# VauDUOv1_0.net
KiCad netlist of a schematic drawn in EAGLE
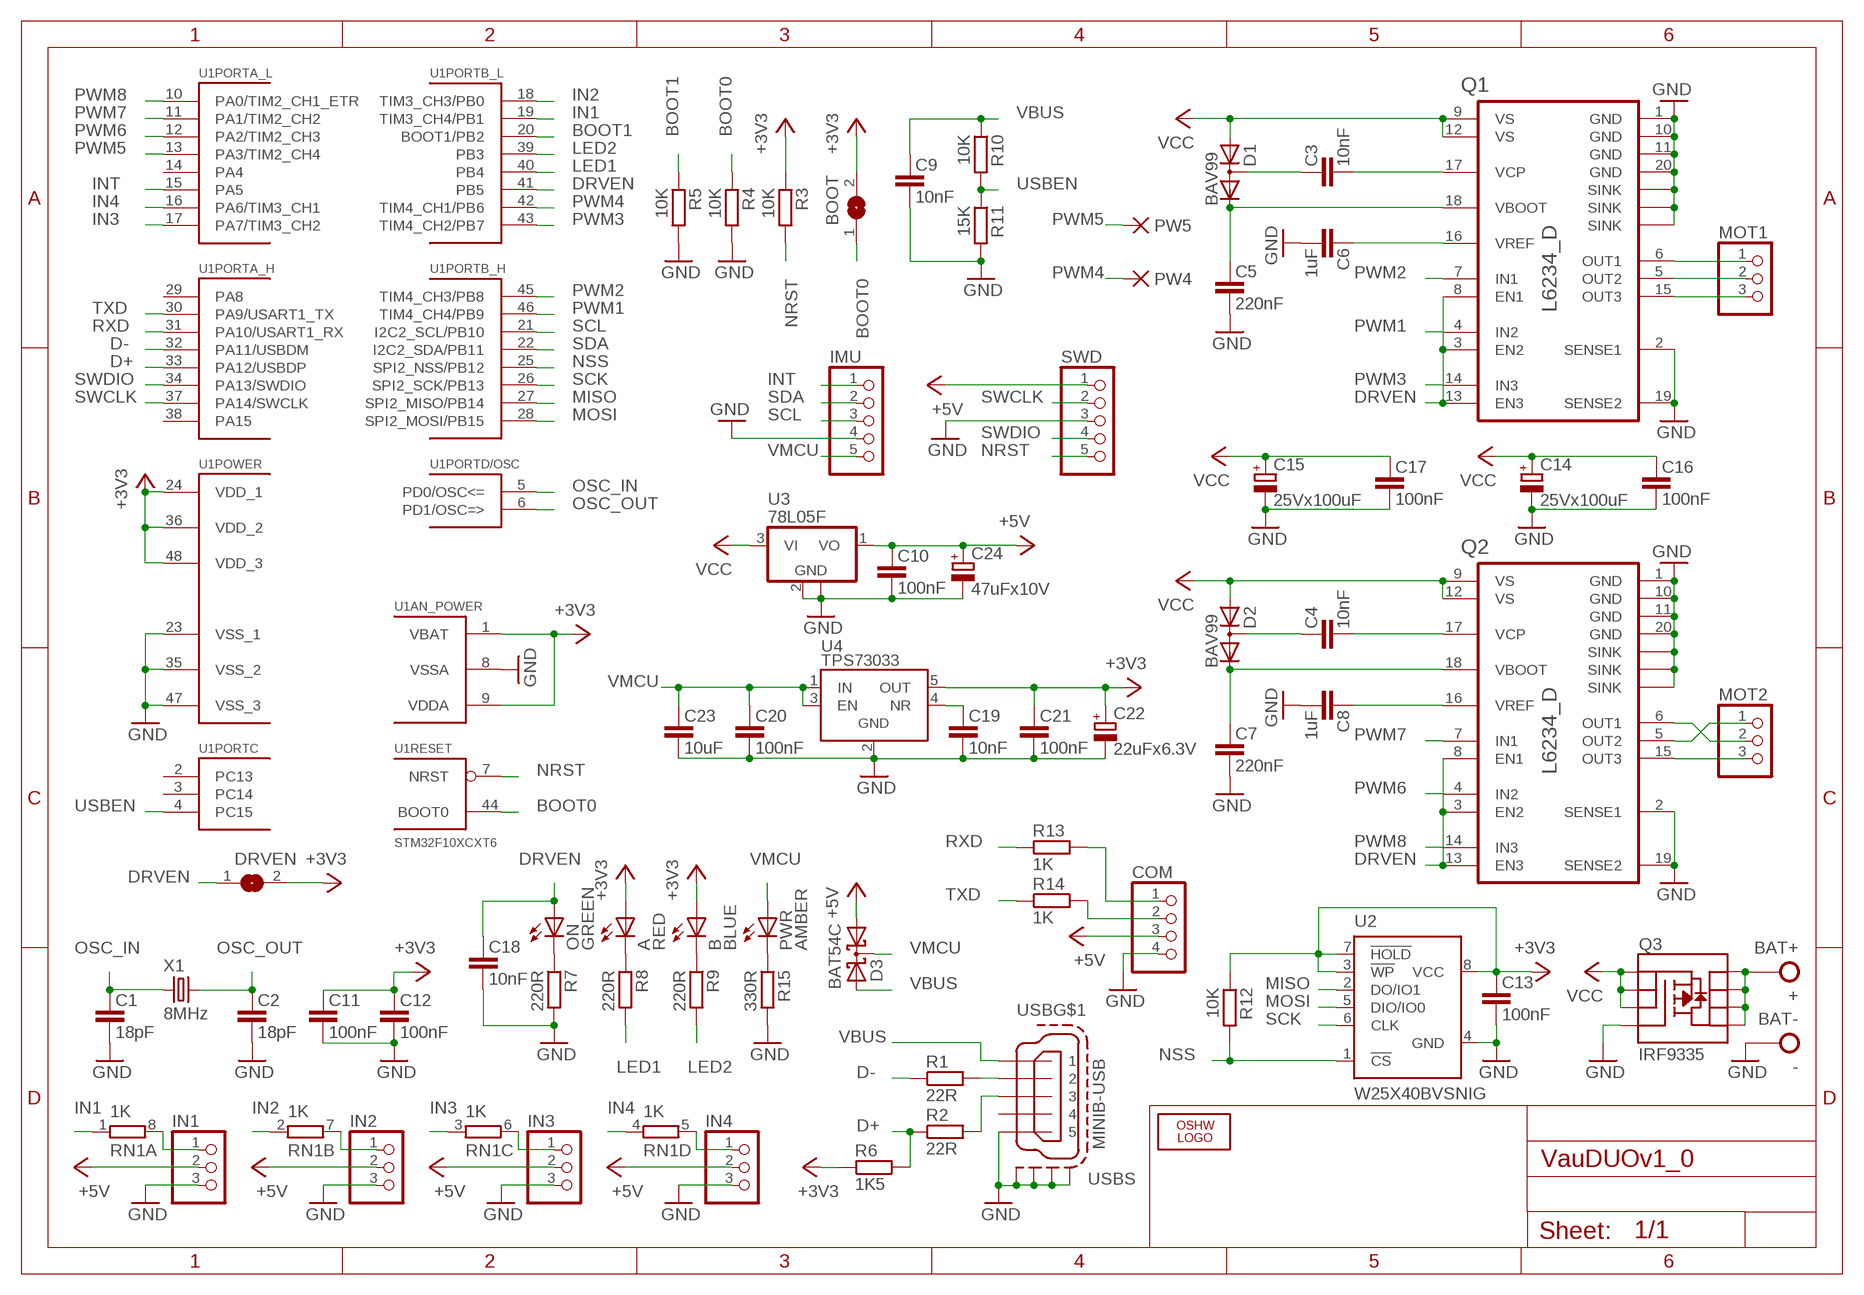
[diagram p0: schematic, sheet 1]

(export (version "E")
  (design (tool "Eeschema 10.0.6"))
  (components
    (comp (ref "+")
      (value "BAT+")
      (footprint "eagle-import:PAD20S")
      (libsource (lib "eagle-import") (part "POWER-PAD-20S"))
    )
    (comp (ref "-")
      (value "BAT-")
      (footprint "eagle-import:PAD20R")
      (libsource (lib "eagle-import") (part "POWER-PAD-20R"))
    )
    (comp (ref "A")
      (value "RED")
      (footprint "eagle-import:CHIPLED_0805")
      (libsource (lib "eagle-import") (part "LEDCHIPLED_0805"))
    )
    (comp (ref "B")
      (value "BLUE")
      (footprint "eagle-import:CHIPLED_0805")
      (libsource (lib "eagle-import") (part "LEDCHIPLED_0805"))
    )
    (comp (ref "BOOT")
      (value "SJ")
      (footprint "eagle-import:SJ")
      (libsource (lib "eagle-import") (part "SJ"))
    )
    (comp (ref "C1")
      (value "18pF")
      (footprint "eagle-import:C0603G")
      (libsource (lib "eagle-import") (part "C_EU_C0603G"))
    )
    (comp (ref "C2")
      (value "18pF")
      (footprint "eagle-import:C0603G")
      (libsource (lib "eagle-import") (part "C_EU_C0603G"))
    )
    (comp (ref "C3")
      (value "10nF")
      (footprint "eagle-import:C0603")
      (libsource (lib "eagle-import") (part "C_EU_C0603"))
    )
    (comp (ref "C4")
      (value "10nF")
      (footprint "eagle-import:C0603")
      (libsource (lib "eagle-import") (part "C_EU_C0603"))
    )
    (comp (ref "C5")
      (value "220nF")
      (footprint "eagle-import:C0603G")
      (libsource (lib "eagle-import") (part "C_EU_C0603G"))
    )
    (comp (ref "C6")
      (value "1uF")
      (footprint "eagle-import:C0603G")
      (libsource (lib "eagle-import") (part "C_EU_C0603G"))
    )
    (comp (ref "C7")
      (value "220nF")
      (footprint "eagle-import:C0603G")
      (libsource (lib "eagle-import") (part "C_EU_C0603G"))
    )
    (comp (ref "C8")
      (value "1uF")
      (footprint "eagle-import:C0603G")
      (libsource (lib "eagle-import") (part "C_EU_C0603G"))
    )
    (comp (ref "C9")
      (value "10nF")
      (footprint "eagle-import:C0603G")
      (libsource (lib "eagle-import") (part "C_EU_C0603G"))
    )
    (comp (ref "C10")
      (value "100nF")
      (footprint "eagle-import:C0603G")
      (libsource (lib "eagle-import") (part "C_EU_C0603G"))
    )
    (comp (ref "C11")
      (value "100nF")
      (footprint "eagle-import:C0603G")
      (libsource (lib "eagle-import") (part "C_EU_C0603G"))
    )
    (comp (ref "C12")
      (value "100nF")
      (footprint "eagle-import:C0603G")
      (libsource (lib "eagle-import") (part "C_EU_C0603G"))
    )
    (comp (ref "C13")
      (value "100nF")
      (footprint "eagle-import:C0603G")
      (libsource (lib "eagle-import") (part "C_EU_C0603G"))
    )
    (comp (ref "C14")
      (value "25Vx100uF")
      (footprint "eagle-import:E2,5-7")
      (libsource (lib "eagle-import") (part "CPOL-EUE2.5-7"))
    )
    (comp (ref "C15")
      (value "25Vx100uF")
      (footprint "eagle-import:E2,5-7")
      (libsource (lib "eagle-import") (part "CPOL-EUE2.5-7"))
    )
    (comp (ref "C16")
      (value "100nF")
      (footprint "eagle-import:C0603G")
      (libsource (lib "eagle-import") (part "C_EU_C0603G"))
    )
    (comp (ref "C17")
      (value "100nF")
      (footprint "eagle-import:C0603G")
      (libsource (lib "eagle-import") (part "C_EU_C0603G"))
    )
    (comp (ref "C18")
      (value "10nF")
      (footprint "eagle-import:C0603G")
      (libsource (lib "eagle-import") (part "C_EU_C0603G"))
    )
    (comp (ref "C19")
      (value "10nF")
      (footprint "eagle-import:C0603G")
      (libsource (lib "eagle-import") (part "C_EU_C0603G"))
    )
    (comp (ref "C20")
      (value "100nF")
      (footprint "eagle-import:C0603G")
      (libsource (lib "eagle-import") (part "C_EU_C0603G"))
    )
    (comp (ref "C21")
      (value "100nF")
      (footprint "eagle-import:C0603G")
      (libsource (lib "eagle-import") (part "C_EU_C0603G"))
    )
    (comp (ref "C22")
      (value "22uFx6.3V")
      (footprint "eagle-import:SMC_A")
      (libsource (lib "eagle-import") (part "CPOL-EUSMCA"))
    )
    (comp (ref "C23")
      (value "10uF")
      (footprint "eagle-import:C0805")
      (libsource (lib "eagle-import") (part "C_EU_C0805"))
    )
    (comp (ref "C24")
      (value "47uFx10V")
      (footprint "eagle-import:SMC_B")
      (libsource (lib "eagle-import") (part "CPOL-EUSMCB"))
    )
    (comp (ref "COM")
      (value "PINHD-1X4")
      (footprint "eagle-import:1X04")
      (libsource (lib "eagle-import") (part "PINHD-1X4"))
    )
    (comp (ref "D1")
      (value "BAV99")
      (footprint "eagle-import:SOT23")
      (libsource (lib "eagle-import") (part "BAV199"))
    )
    (comp (ref "D2")
      (value "BAV99")
      (footprint "eagle-import:SOT23")
      (libsource (lib "eagle-import") (part "BAV199"))
    )
    (comp (ref "D3")
      (value "BAT54C")
      (footprint "eagle-import:SOT23")
      (libsource (lib "eagle-import") (part "BAT54C"))
    )
    (comp (ref "DRVEN")
      (value "SJ")
      (footprint "eagle-import:SJ")
      (libsource (lib "eagle-import") (part "SJ"))
    )
    (comp (ref "IMU")
      (value "PINHD-1X5")
      (footprint "eagle-import:1X05")
      (libsource (lib "eagle-import") (part "PINHD-1X5"))
    )
    (comp (ref "IN1")
      (value "PINHD-1X3")
      (footprint "eagle-import:1X03")
      (libsource (lib "eagle-import") (part "PINHD-1X3"))
    )
    (comp (ref "IN2")
      (value "PINHD-1X3")
      (footprint "eagle-import:1X03")
      (libsource (lib "eagle-import") (part "PINHD-1X3"))
    )
    (comp (ref "IN3")
      (value "PINHD-1X3")
      (footprint "eagle-import:1X03")
      (libsource (lib "eagle-import") (part "PINHD-1X3"))
    )
    (comp (ref "IN4")
      (value "PINHD-1X3")
      (footprint "eagle-import:1X03")
      (libsource (lib "eagle-import") (part "PINHD-1X3"))
    )
    (comp (ref "LOGO1")
      (value "OSHW_LOGO_10MILX0350-NT")
      (footprint "eagle-import:OSHW_10X350_NOTEXT")
      (libsource (lib "eagle-import") (part "OSHW_LOGO_10MILX0350-NT"))
    )
    (comp (ref "MOT1")
      (value "PINHD-1X3MOT")
      (footprint "eagle-import:1X03M")
      (libsource (lib "eagle-import") (part "PINHD-1X3MOT"))
    )
    (comp (ref "MOT2")
      (value "PINHD-1X3MOT")
      (footprint "eagle-import:1X03M")
      (libsource (lib "eagle-import") (part "PINHD-1X3MOT"))
    )
    (comp (ref "ON")
      (value "GREEN")
      (footprint "eagle-import:CHIPLED_0805")
      (libsource (lib "eagle-import") (part "LEDCHIPLED_0805"))
    )
    (comp (ref "PW4")
      (value "PAD-SMD09R")
      (footprint "eagle-import:SMD09R")
      (libsource (lib "eagle-import") (part "PAD-SMD09R"))
    )
    (comp (ref "PW5")
      (value "PAD-SMD09R")
      (footprint "eagle-import:SMD09R")
      (libsource (lib "eagle-import") (part "PAD-SMD09R"))
    )
    (comp (ref "PWR")
      (value "AMBER")
      (footprint "eagle-import:CHIPLED_0805")
      (libsource (lib "eagle-import") (part "LEDCHIPLED_0805"))
    )
    (comp (ref "Q1")
      (value "L6234_D")
      (footprint "eagle-import:POWERSO20")
      (libsource (lib "eagle-import") (part "L6234_D"))
    )
    (comp (ref "Q2")
      (value "L6234_D")
      (footprint "eagle-import:POWERSO20")
      (libsource (lib "eagle-import") (part "L6234_D"))
    )
    (comp (ref "Q3")
      (value "IRF9335")
      (footprint "eagle-import:SOIC-8")
      (libsource (lib "eagle-import") (part "MOSFET-PCHANNEL-SOIC8"))
    )
    (comp (ref "R1")
      (value "22R")
      (footprint "eagle-import:R0603")
      (libsource (lib "eagle-import") (part "R_EU_R0603"))
    )
    (comp (ref "R2")
      (value "22R")
      (footprint "eagle-import:R0603")
      (libsource (lib "eagle-import") (part "R_EU_R0603"))
    )
    (comp (ref "R3")
      (value "10K")
      (footprint "eagle-import:R0603")
      (libsource (lib "eagle-import") (part "R_EU_R0603"))
    )
    (comp (ref "R4")
      (value "10K")
      (footprint "eagle-import:R0603G")
      (libsource (lib "eagle-import") (part "R_EU_R0603G"))
    )
    (comp (ref "R5")
      (value "10K")
      (footprint "eagle-import:R0603G")
      (libsource (lib "eagle-import") (part "R_EU_R0603G"))
    )
    (comp (ref "R6")
      (value "1K5")
      (footprint "eagle-import:R0603")
      (libsource (lib "eagle-import") (part "R_EU_R0603"))
    )
    (comp (ref "R7")
      (value "220R")
      (footprint "eagle-import:R0603G")
      (libsource (lib "eagle-import") (part "R_EU_R0603G"))
    )
    (comp (ref "R8")
      (value "220R")
      (footprint "eagle-import:R0603")
      (libsource (lib "eagle-import") (part "R_EU_R0603"))
    )
    (comp (ref "R9")
      (value "220R")
      (footprint "eagle-import:R0603")
      (libsource (lib "eagle-import") (part "R_EU_R0603"))
    )
    (comp (ref "R10")
      (value "10K")
      (footprint "eagle-import:R0603")
      (libsource (lib "eagle-import") (part "R_EU_R0603"))
    )
    (comp (ref "R11")
      (value "15K")
      (footprint "eagle-import:R0603G")
      (libsource (lib "eagle-import") (part "R_EU_R0603G"))
    )
    (comp (ref "R12")
      (value "10K")
      (footprint "eagle-import:R0603")
      (libsource (lib "eagle-import") (part "R_EU_R0603"))
    )
    (comp (ref "R13")
      (value "1K")
      (footprint "eagle-import:R0603")
      (libsource (lib "eagle-import") (part "R_EU_R0603"))
    )
    (comp (ref "R14")
      (value "1K")
      (footprint "eagle-import:R0603")
      (libsource (lib "eagle-import") (part "R_EU_R0603"))
    )
    (comp (ref "R15")
      (value "330R")
      (footprint "eagle-import:R0603")
      (libsource (lib "eagle-import") (part "R_EU_R0603"))
    )
    (comp (ref "RN1")
      (value "1K")
      (footprint "eagle-import:CAY16")
      (libsource (lib "eagle-import") (part "4R-NCAY16"))
    )
    (comp (ref "SWD")
      (value "PINHD-1X5")
      (footprint "eagle-import:1X05")
      (libsource (lib "eagle-import") (part "PINHD-1X5"))
    )
    (comp (ref "U1")
      (value "STM32F10XCXT6")
      (footprint "eagle-import:LQFP48")
      (libsource (lib "eagle-import") (part "STM32F10XCXT6"))
    )
    (comp (ref "U2")
      (value "W25X40BVSNIG")
      (footprint "eagle-import:SOIC-8")
      (libsource (lib "eagle-import") (part "W25X40BVSNIG"))
    )
    (comp (ref "U3")
      (value "78L05F")
      (footprint "eagle-import:SOT89")
      (libsource (lib "eagle-import") (part "78LF05"))
    )
    (comp (ref "U4")
      (value "TPS73033")
      (footprint "eagle-import:SOT23-5")
      (libsource (lib "eagle-import") (part "TPS769XX"))
    )
    (comp (ref "USB")
      (value "MINIB-USB")
      (footprint "eagle-import:32005-201")
      (libsource (lib "eagle-import") (part "MINI-USB-SCHIELD-32005-201"))
    )
    (comp (ref "X1")
      (value "8MHz")
      (footprint "eagle-import:HC49_S")
      (libsource (lib "eagle-import") (part "CRYSTALHC49S"))
    )
  )
  (nets
    (net (code "1") (name "+3V3") (class "Default")
      (node (ref "A") (pin "A") (pinfunction "A_A") (pintype "passive"))
      (node (ref "B") (pin "A") (pinfunction "A_A") (pintype "passive"))
      (node (ref "BOOT") (pin "2") (pinfunction "2_2") (pintype "passive"))
      (node (ref "C11") (pin "1") (pinfunction "1_1") (pintype "passive"))
      (node (ref "C12") (pin "1") (pinfunction "1_1") (pintype "passive"))
      (node (ref "C13") (pin "1") (pinfunction "1_1") (pintype "passive"))
      (node (ref "C21") (pin "1") (pinfunction "1_1") (pintype "passive"))
      (node (ref "C22") (pin "+") (pinfunction "+_+") (pintype "passive"))
      (node (ref "DRVEN") (pin "2") (pinfunction "2_2") (pintype "passive"))
      (node (ref "R12") (pin "1") (pinfunction "1_1") (pintype "passive"))
      (node (ref "R3") (pin "1") (pinfunction "1_1") (pintype "passive"))
      (node (ref "R6") (pin "1") (pinfunction "1_1") (pintype "passive"))
      (node (ref "U1") (pin "1") (pinfunction "VBAT_1") (pintype "power_in"))
      (node (ref "U1") (pin "24") (pinfunction "VDD_1_24") (pintype "power_in"))
      (node (ref "U1") (pin "36") (pinfunction "VDD_2_36") (pintype "power_in"))
      (node (ref "U1") (pin "48") (pinfunction "VDD_3_48") (pintype "power_in"))
      (node (ref "U1") (pin "9") (pinfunction "VDDA_9") (pintype "power_in"))
      (node (ref "U2") (pin "3") (pinfunction "~{WP}_3") (pintype "input"))
      (node (ref "U2") (pin "7") (pinfunction "~{HOLD}_7") (pintype "input"))
      (node (ref "U2") (pin "8") (pinfunction "VCC_8") (pintype "power_in"))
      (node (ref "U4") (pin "5") (pinfunction "OUT_5") (pintype "power_in"))
    )
    (net (code "2") (name "+5V") (class "Default")
      (node (ref "C10") (pin "1") (pinfunction "1_1") (pintype "passive"))
      (node (ref "C24") (pin "+") (pinfunction "+_+") (pintype "passive"))
      (node (ref "COM") (pin "3") (pinfunction "3_3") (pintype "passive"))
      (node (ref "D3") (pin "1") (pinfunction "A1_1") (pintype "passive"))
      (node (ref "IN1") (pin "2") (pinfunction "2_2") (pintype "passive"))
      (node (ref "IN2") (pin "2") (pinfunction "2_2") (pintype "passive"))
      (node (ref "IN3") (pin "2") (pinfunction "2_2") (pintype "passive"))
      (node (ref "IN4") (pin "2") (pinfunction "2_2") (pintype "passive"))
      (node (ref "SWD") (pin "1") (pinfunction "1_1") (pintype "passive"))
      (node (ref "U3") (pin "1") (pinfunction "VO_1") (pintype "passive"))
    )
    (net (code "3") (name "/BOOT0") (class "Default")
      (node (ref "BOOT") (pin "1") (pinfunction "1_1") (pintype "passive"))
      (node (ref "R4") (pin "1") (pinfunction "1_1") (pintype "passive"))
      (node (ref "U1") (pin "44") (pinfunction "BOOT0_44") (pintype "input"))
    )
    (net (code "4") (name "/BOOT1") (class "Default")
      (node (ref "R5") (pin "1") (pinfunction "1_1") (pintype "passive"))
      (node (ref "U1") (pin "20") (pinfunction "BOOT1/PB2_20") (pintype "bidirectional"))
    )
    (net (code "5") (name "/D+") (class "Default")
      (node (ref "R2") (pin "1") (pinfunction "1_1") (pintype "passive"))
      (node (ref "R6") (pin "2") (pinfunction "2_2") (pintype "passive"))
      (node (ref "U1") (pin "33") (pinfunction "PA12/USBDP_33") (pintype "bidirectional"))
    )
    (net (code "6") (name "/D-") (class "Default")
      (node (ref "R1") (pin "1") (pinfunction "1_1") (pintype "passive"))
      (node (ref "U1") (pin "32") (pinfunction "PA11/USBDM_32") (pintype "bidirectional"))
    )
    (net (code "7") (name "/DRVEN") (class "Default")
      (node (ref "C18") (pin "1") (pinfunction "1_1") (pintype "passive"))
      (node (ref "DRVEN") (pin "1") (pinfunction "1_1") (pintype "passive"))
      (node (ref "ON") (pin "A") (pinfunction "A_A") (pintype "passive"))
      (node (ref "Q1") (pin "13") (pinfunction "EN3_13") (pintype "input"))
      (node (ref "Q1") (pin "3") (pinfunction "EN2_3") (pintype "input"))
      (node (ref "Q1") (pin "8") (pinfunction "EN1_8") (pintype "input"))
      (node (ref "Q2") (pin "13") (pinfunction "EN3_13") (pintype "input"))
      (node (ref "Q2") (pin "3") (pinfunction "EN2_3") (pintype "input"))
      (node (ref "Q2") (pin "8") (pinfunction "EN1_8") (pintype "input"))
      (node (ref "U1") (pin "41") (pinfunction "PB5_41") (pintype "bidirectional"))
    )
    (net (code "8") (name "/IN1") (class "Default")
      (node (ref "RN1") (pin "1") (pinfunction "1_1") (pintype "passive"))
      (node (ref "U1") (pin "19") (pinfunction "TIM3_CH4/PB1_19") (pintype "bidirectional"))
    )
    (net (code "9") (name "/IN2") (class "Default")
      (node (ref "RN1") (pin "2") (pinfunction "1_2") (pintype "passive"))
      (node (ref "U1") (pin "18") (pinfunction "TIM3_CH3/PB0_18") (pintype "bidirectional"))
    )
    (net (code "10") (name "/IN3") (class "Default")
      (node (ref "RN1") (pin "3") (pinfunction "1_3") (pintype "passive"))
      (node (ref "U1") (pin "17") (pinfunction "PA7/TIM3_CH2_17") (pintype "bidirectional"))
    )
    (net (code "11") (name "/IN4") (class "Default")
      (node (ref "RN1") (pin "4") (pinfunction "1_4") (pintype "passive"))
      (node (ref "U1") (pin "16") (pinfunction "PA6/TIM3_CH1_16") (pintype "bidirectional"))
    )
    (net (code "12") (name "/INT") (class "Default")
      (node (ref "IMU") (pin "1") (pinfunction "1_1") (pintype "passive"))
      (node (ref "U1") (pin "15") (pinfunction "PA5_15") (pintype "bidirectional"))
    )
    (net (code "13") (name "/LED1") (class "Default")
      (node (ref "R8") (pin "2") (pinfunction "2_2") (pintype "passive"))
      (node (ref "U1") (pin "40") (pinfunction "PB4_40") (pintype "bidirectional"))
    )
    (net (code "14") (name "/LED2") (class "Default")
      (node (ref "R9") (pin "2") (pinfunction "2_2") (pintype "passive"))
      (node (ref "U1") (pin "39") (pinfunction "PB3_39") (pintype "bidirectional"))
    )
    (net (code "15") (name "/MISO") (class "Default")
      (node (ref "U1") (pin "27") (pinfunction "SPI2_MISO/PB14_27") (pintype "bidirectional"))
      (node (ref "U2") (pin "2") (pinfunction "DO/IO1_2") (pintype "output"))
    )
    (net (code "16") (name "/MOSI") (class "Default")
      (node (ref "U1") (pin "28") (pinfunction "SPI2_MOSI/PB15_28") (pintype "bidirectional"))
      (node (ref "U2") (pin "5") (pinfunction "DIO/IO0_5") (pintype "bidirectional"))
    )
    (net (code "17") (name "/NRST") (class "Default")
      (node (ref "R3") (pin "2") (pinfunction "2_2") (pintype "passive"))
      (node (ref "SWD") (pin "5") (pinfunction "5_5") (pintype "passive"))
      (node (ref "U1") (pin "7") (pinfunction "NRST_7") (pintype "input"))
    )
    (net (code "18") (name "/NSS") (class "Default")
      (node (ref "R12") (pin "2") (pinfunction "2_2") (pintype "passive"))
      (node (ref "U1") (pin "25") (pinfunction "SPI2_NSS/PB12_25") (pintype "bidirectional"))
      (node (ref "U2") (pin "1") (pinfunction "~{CS}_1") (pintype "input"))
    )
    (net (code "19") (name "/OSC_IN") (class "Default")
      (node (ref "C1") (pin "1") (pinfunction "1_1") (pintype "passive"))
      (node (ref "U1") (pin "5") (pinfunction "PD0/OSC<=_5") (pintype "bidirectional"))
      (node (ref "X1") (pin "1") (pinfunction "1_1") (pintype "passive"))
    )
    (net (code "20") (name "/OSC_OUT") (class "Default")
      (node (ref "C2") (pin "1") (pinfunction "1_1") (pintype "passive"))
      (node (ref "U1") (pin "6") (pinfunction "PD1/OSC=>_6") (pintype "bidirectional"))
      (node (ref "X1") (pin "2") (pinfunction "2_2") (pintype "passive"))
    )
    (net (code "21") (name "/PWM1") (class "Default")
      (node (ref "Q1") (pin "4") (pinfunction "IN2_4") (pintype "input"))
      (node (ref "U1") (pin "46") (pinfunction "TIM4_CH4/PB9_46") (pintype "bidirectional"))
    )
    (net (code "22") (name "/PWM2") (class "Default")
      (node (ref "Q1") (pin "7") (pinfunction "IN1_7") (pintype "input"))
      (node (ref "U1") (pin "45") (pinfunction "TIM4_CH3/PB8_45") (pintype "bidirectional"))
    )
    (net (code "23") (name "/PWM3") (class "Default")
      (node (ref "Q1") (pin "14") (pinfunction "IN3_14") (pintype "input"))
      (node (ref "U1") (pin "43") (pinfunction "TIM4_CH2/PB7_43") (pintype "bidirectional"))
    )
    (net (code "24") (name "/PWM4") (class "Default")
      (node (ref "PW4") (pin "PAD") (pinfunction "P_PAD") (pintype "passive"))
      (node (ref "U1") (pin "42") (pinfunction "TIM4_CH1/PB6_42") (pintype "bidirectional"))
    )
    (net (code "25") (name "/PWM5") (class "Default")
      (node (ref "PW5") (pin "PAD") (pinfunction "P_PAD") (pintype "passive"))
      (node (ref "U1") (pin "13") (pinfunction "PA3/TIM2_CH4_13") (pintype "bidirectional"))
    )
    (net (code "26") (name "/PWM6") (class "Default")
      (node (ref "Q2") (pin "4") (pinfunction "IN2_4") (pintype "input"))
      (node (ref "U1") (pin "12") (pinfunction "PA2/TIM2_CH3_12") (pintype "bidirectional"))
    )
    (net (code "27") (name "/PWM7") (class "Default")
      (node (ref "Q2") (pin "7") (pinfunction "IN1_7") (pintype "input"))
      (node (ref "U1") (pin "11") (pinfunction "PA1/TIM2_CH2_11") (pintype "bidirectional"))
    )
    (net (code "28") (name "/PWM8") (class "Default")
      (node (ref "Q2") (pin "14") (pinfunction "IN3_14") (pintype "input"))
      (node (ref "U1") (pin "10") (pinfunction "PA0/TIM2_CH1_ETR_10") (pintype "bidirectional"))
    )
    (net (code "29") (name "/RXD") (class "Default")
      (node (ref "R13") (pin "1") (pinfunction "1_1") (pintype "passive"))
      (node (ref "U1") (pin "31") (pinfunction "PA10/USART1_RX_31") (pintype "bidirectional"))
    )
    (net (code "30") (name "/SCK") (class "Default")
      (node (ref "U1") (pin "26") (pinfunction "SPI2_SCK/PB13_26") (pintype "bidirectional"))
      (node (ref "U2") (pin "6") (pinfunction "CLK_6") (pintype "input"))
    )
    (net (code "31") (name "/SCL") (class "Default")
      (node (ref "IMU") (pin "3") (pinfunction "3_3") (pintype "passive"))
      (node (ref "U1") (pin "21") (pinfunction "I2C2_SCL/PB10_21") (pintype "bidirectional"))
    )
    (net (code "32") (name "/SDA") (class "Default")
      (node (ref "IMU") (pin "2") (pinfunction "2_2") (pintype "passive"))
      (node (ref "U1") (pin "22") (pinfunction "I2C2_SDA/PB11_22") (pintype "bidirectional"))
    )
    (net (code "33") (name "/SWCLK") (class "Default")
      (node (ref "SWD") (pin "2") (pinfunction "2_2") (pintype "passive"))
      (node (ref "U1") (pin "37") (pinfunction "PA14/SWCLK_37") (pintype "bidirectional"))
    )
    (net (code "34") (name "/SWDIO") (class "Default")
      (node (ref "SWD") (pin "4") (pinfunction "4_4") (pintype "passive"))
      (node (ref "U1") (pin "34") (pinfunction "PA13/SWDIO_34") (pintype "bidirectional"))
    )
    (net (code "35") (name "/TXD") (class "Default")
      (node (ref "R14") (pin "1") (pinfunction "1_1") (pintype "passive"))
      (node (ref "U1") (pin "30") (pinfunction "PA9/USART1_TX_30") (pintype "bidirectional"))
    )
    (net (code "36") (name "/USBEN") (class "Default")
      (node (ref "R10") (pin "2") (pinfunction "2_2") (pintype "passive"))
      (node (ref "R11") (pin "1") (pinfunction "1_1") (pintype "passive"))
      (node (ref "U1") (pin "4") (pinfunction "PC15_4") (pintype "bidirectional"))
    )
    (net (code "37") (name "/VBUS") (class "Default")
      (node (ref "C9") (pin "1") (pinfunction "1_1") (pintype "passive"))
      (node (ref "D3") (pin "2") (pinfunction "A2_2") (pintype "passive"))
      (node (ref "R10") (pin "1") (pinfunction "1_1") (pintype "passive"))
      (node (ref "USB") (pin "1") (pinfunction "1_1") (pintype "passive"))
    )
    (net (code "38") (name "/VMCU") (class "Default")
      (node (ref "C20") (pin "1") (pinfunction "1_1") (pintype "passive"))
      (node (ref "C23") (pin "1") (pinfunction "1_1") (pintype "passive"))
      (node (ref "D3") (pin "3") (pinfunction "CC_3") (pintype "passive"))
      (node (ref "IMU") (pin "5") (pinfunction "5_5") (pintype "passive"))
      (node (ref "PWR") (pin "A") (pinfunction "A_A") (pintype "passive"))
      (node (ref "U4") (pin "1") (pinfunction "IN_1") (pintype "power_in"))
      (node (ref "U4") (pin "3") (pinfunction "EN_3") (pintype "passive"))
    )
    (net (code "39") (name "GND") (class "Default")
      (node (ref "-") (pin "P$1") (pinfunction "1_P$1") (pintype "bidirectional"))
      (node (ref "C1") (pin "2") (pinfunction "2_2") (pintype "passive"))
      (node (ref "C10") (pin "2") (pinfunction "2_2") (pintype "passive"))
      (node (ref "C11") (pin "2") (pinfunction "2_2") (pintype "passive"))
      (node (ref "C12") (pin "2") (pinfunction "2_2") (pintype "passive"))
      (node (ref "C13") (pin "2") (pinfunction "2_2") (pintype "passive"))
      (node (ref "C14") (pin "-") (pinfunction "-_-") (pintype "passive"))
      (node (ref "C15") (pin "-") (pinfunction "-_-") (pintype "passive"))
      (node (ref "C16") (pin "2") (pinfunction "2_2") (pintype "passive"))
      (node (ref "C17") (pin "2") (pinfunction "2_2") (pintype "passive"))
      (node (ref "C18") (pin "2") (pinfunction "2_2") (pintype "passive"))
      (node (ref "C19") (pin "2") (pinfunction "2_2") (pintype "passive"))
      (node (ref "C2") (pin "2") (pinfunction "2_2") (pintype "passive"))
      (node (ref "C20") (pin "2") (pinfunction "2_2") (pintype "passive"))
      (node (ref "C21") (pin "2") (pinfunction "2_2") (pintype "passive"))
      (node (ref "C22") (pin "-") (pinfunction "-_-") (pintype "passive"))
      (node (ref "C23") (pin "2") (pinfunction "2_2") (pintype "passive"))
      (node (ref "C24") (pin "-") (pinfunction "-_-") (pintype "passive"))
      (node (ref "C5") (pin "2") (pinfunction "2_2") (pintype "passive"))
      (node (ref "C6") (pin "2") (pinfunction "2_2") (pintype "passive"))
      (node (ref "C7") (pin "2") (pinfunction "2_2") (pintype "passive"))
      (node (ref "C8") (pin "2") (pinfunction "2_2") (pintype "passive"))
      (node (ref "C9") (pin "2") (pinfunction "2_2") (pintype "passive"))
      (node (ref "COM") (pin "4") (pinfunction "4_4") (pintype "passive"))
      (node (ref "IMU") (pin "4") (pinfunction "4_4") (pintype "passive"))
      (node (ref "IN1") (pin "3") (pinfunction "3_3") (pintype "passive"))
      (node (ref "IN2") (pin "3") (pinfunction "3_3") (pintype "passive"))
      (node (ref "IN3") (pin "3") (pinfunction "3_3") (pintype "passive"))
      (node (ref "IN4") (pin "3") (pinfunction "3_3") (pintype "passive"))
      (node (ref "Q1") (pin "1") (pinfunction "GND_1") (pintype "power_in"))
      (node (ref "Q1") (pin "10") (pinfunction "GND_10") (pintype "power_in"))
      (node (ref "Q1") (pin "11") (pinfunction "GND_11") (pintype "power_in"))
      (node (ref "Q1") (pin "19") (pinfunction "SENSE2_19") (pintype "input"))
      (node (ref "Q1") (pin "2") (pinfunction "SENSE1_2") (pintype "input"))
      (node (ref "Q1") (pin "20") (pinfunction "GND_20") (pintype "power_in"))
      (node (ref "Q1") (pin "SINK1") (pinfunction "SINK_SINK1") (pintype "passive"))
      (node (ref "Q1") (pin "SINK2") (pinfunction "SINK_SINK2") (pintype "passive"))
      (node (ref "Q1") (pin "SINK3") (pinfunction "SINK_SINK3") (pintype "passive"))
      (node (ref "Q2") (pin "1") (pinfunction "GND_1") (pintype "power_in"))
      (node (ref "Q2") (pin "10") (pinfunction "GND_10") (pintype "power_in"))
      (node (ref "Q2") (pin "11") (pinfunction "GND_11") (pintype "power_in"))
      (node (ref "Q2") (pin "19") (pinfunction "SENSE2_19") (pintype "input"))
      (node (ref "Q2") (pin "2") (pinfunction "SENSE1_2") (pintype "input"))
      (node (ref "Q2") (pin "20") (pinfunction "GND_20") (pintype "power_in"))
      (node (ref "Q2") (pin "SINK1") (pinfunction "SINK_SINK1") (pintype "passive"))
      (node (ref "Q2") (pin "SINK2") (pinfunction "SINK_SINK2") (pintype "passive"))
      (node (ref "Q2") (pin "SINK3") (pinfunction "SINK_SINK3") (pintype "passive"))
      (node (ref "Q3") (pin "4") (pinfunction "G_4") (pintype "bidirectional"))
      (node (ref "R11") (pin "2") (pinfunction "2_2") (pintype "passive"))
      (node (ref "R15") (pin "2") (pinfunction "2_2") (pintype "passive"))
      (node (ref "R4") (pin "2") (pinfunction "2_2") (pintype "passive"))
      (node (ref "R5") (pin "2") (pinfunction "2_2") (pintype "passive"))
      (node (ref "R7") (pin "2") (pinfunction "2_2") (pintype "passive"))
      (node (ref "SWD") (pin "3") (pinfunction "3_3") (pintype "passive"))
      (node (ref "U1") (pin "23") (pinfunction "VSS_1_23") (pintype "power_in"))
      (node (ref "U1") (pin "35") (pinfunction "VSS_2_35") (pintype "power_in"))
      (node (ref "U1") (pin "47") (pinfunction "VSS_3_47") (pintype "power_in"))
      (node (ref "U1") (pin "8") (pinfunction "VSSA_8") (pintype "power_in"))
      (node (ref "U2") (pin "4") (pinfunction "GND_4") (pintype "power_in"))
      (node (ref "U3") (pin "2") (pinfunction "GND_2") (pintype "passive"))
      (node (ref "U3") (pin "2@1") (pinfunction "GND_2@1") (pintype "passive"))
      (node (ref "U4") (pin "2") (pinfunction "GND_2") (pintype "power_in"))
      (node (ref "USB") (pin "5") (pinfunction "5_5") (pintype "passive"))
      (node (ref "USB") (pin "M1") (pinfunction "S1_M1") (pintype "passive"))
      (node (ref "USB") (pin "M2") (pinfunction "S2_M2") (pintype "passive"))
      (node (ref "USB") (pin "M3") (pinfunction "S3_M3") (pintype "passive"))
      (node (ref "USB") (pin "M4") (pinfunction "S4_M4") (pintype "passive"))
    )
    (net (code "40") (name "Net-(+-1)") (class "Default")
      (node (ref "+") (pin "P$1") (pinfunction "1_P$1") (pintype "bidirectional"))
      (node (ref "Q3") (pin "5") (pinfunction "D_5") (pintype "bidirectional"))
      (node (ref "Q3") (pin "6") (pinfunction "D_6") (pintype "bidirectional"))
      (node (ref "Q3") (pin "7") (pinfunction "D_7") (pintype "bidirectional"))
      (node (ref "Q3") (pin "8") (pinfunction "D_8") (pintype "bidirectional"))
    )
    (net (code "41") (name "Net-(A-PadC)") (class "Default")
      (node (ref "A") (pin "C") (pinfunction "C_C") (pintype "passive"))
      (node (ref "R8") (pin "1") (pinfunction "1_1") (pintype "passive"))
    )
    (net (code "42") (name "Net-(B-PadC)") (class "Default")
      (node (ref "B") (pin "C") (pinfunction "C_C") (pintype "passive"))
      (node (ref "R9") (pin "1") (pinfunction "1_1") (pintype "passive"))
    )
    (net (code "43") (name "Net-(COM-Pad1)") (class "Default")
      (node (ref "COM") (pin "1") (pinfunction "1_1") (pintype "passive"))
      (node (ref "R13") (pin "2") (pinfunction "2_2") (pintype "passive"))
    )
    (net (code "44") (name "Net-(COM-Pad2)") (class "Default")
      (node (ref "COM") (pin "2") (pinfunction "2_2") (pintype "passive"))
      (node (ref "R14") (pin "2") (pinfunction "2_2") (pintype "passive"))
    )
    (net (code "45") (name "Net-(D1-AC)") (class "Default")
      (node (ref "C3") (pin "1") (pinfunction "1_1") (pintype "passive"))
      (node (ref "D1") (pin "3") (pinfunction "AC_3") (pintype "passive"))
    )
    (net (code "46") (name "Net-(D1-C)") (class "Default")
      (node (ref "C5") (pin "1") (pinfunction "1_1") (pintype "passive"))
      (node (ref "D1") (pin "2") (pinfunction "C_2") (pintype "passive"))
      (node (ref "Q1") (pin "18") (pinfunction "VBOOT_18") (pintype "input"))
    )
    (net (code "47") (name "Net-(D2-AC)") (class "Default")
      (node (ref "C4") (pin "1") (pinfunction "1_1") (pintype "passive"))
      (node (ref "D2") (pin "3") (pinfunction "AC_3") (pintype "passive"))
    )
    (net (code "48") (name "Net-(D2-C)") (class "Default")
      (node (ref "C7") (pin "1") (pinfunction "1_1") (pintype "passive"))
      (node (ref "D2") (pin "2") (pinfunction "C_2") (pintype "passive"))
      (node (ref "Q2") (pin "18") (pinfunction "VBOOT_18") (pintype "input"))
    )
    (net (code "49") (name "Net-(ON-PadC)") (class "Default")
      (node (ref "ON") (pin "C") (pinfunction "C_C") (pintype "passive"))
      (node (ref "R7") (pin "1") (pinfunction "1_1") (pintype "passive"))
    )
    (net (code "50") (name "Net-(PWR-PadC)") (class "Default")
      (node (ref "PWR") (pin "C") (pinfunction "C_C") (pintype "passive"))
      (node (ref "R15") (pin "1") (pinfunction "1_1") (pintype "passive"))
    )
    (net (code "51") (name "Net-(Q1-OUT1)") (class "Default")
      (node (ref "MOT1") (pin "1") (pinfunction "1_1") (pintype "passive"))
      (node (ref "Q1") (pin "6") (pinfunction "OUT1_6") (pintype "output"))
    )
    (net (code "52") (name "Net-(Q1-OUT2)") (class "Default")
      (node (ref "MOT1") (pin "2") (pinfunction "2_2") (pintype "passive"))
      (node (ref "Q1") (pin "5") (pinfunction "OUT2_5") (pintype "output"))
    )
    (net (code "53") (name "Net-(Q1-OUT3)") (class "Default")
      (node (ref "MOT1") (pin "3") (pinfunction "3_3") (pintype "passive"))
      (node (ref "Q1") (pin "15") (pinfunction "OUT3_15") (pintype "output"))
    )
    (net (code "54") (name "Net-(Q1-VCP)") (class "Default")
      (node (ref "C3") (pin "2") (pinfunction "2_2") (pintype "passive"))
      (node (ref "Q1") (pin "17") (pinfunction "VCP_17") (pintype "output"))
    )
    (net (code "55") (name "Net-(Q1-VREF)") (class "Default")
      (node (ref "C6") (pin "1") (pinfunction "1_1") (pintype "passive"))
      (node (ref "Q1") (pin "16") (pinfunction "VREF_16") (pintype "passive"))
    )
    (net (code "56") (name "Net-(Q2-OUT1)") (class "Default")
      (node (ref "MOT2") (pin "2") (pinfunction "2_2") (pintype "passive"))
      (node (ref "Q2") (pin "6") (pinfunction "OUT1_6") (pintype "output"))
    )
    (net (code "57") (name "Net-(Q2-OUT2)") (class "Default")
      (node (ref "MOT2") (pin "1") (pinfunction "1_1") (pintype "passive"))
      (node (ref "Q2") (pin "5") (pinfunction "OUT2_5") (pintype "output"))
    )
    (net (code "58") (name "Net-(Q2-OUT3)") (class "Default")
      (node (ref "MOT2") (pin "3") (pinfunction "3_3") (pintype "passive"))
      (node (ref "Q2") (pin "15") (pinfunction "OUT3_15") (pintype "output"))
    )
    (net (code "59") (name "Net-(Q2-VCP)") (class "Default")
      (node (ref "C4") (pin "2") (pinfunction "2_2") (pintype "passive"))
      (node (ref "Q2") (pin "17") (pinfunction "VCP_17") (pintype "output"))
    )
    (net (code "60") (name "Net-(Q2-VREF)") (class "Default")
      (node (ref "C8") (pin "1") (pinfunction "1_1") (pintype "passive"))
      (node (ref "Q2") (pin "16") (pinfunction "VREF_16") (pintype "passive"))
    )
    (net (code "61") (name "Net-(R1-Pad2)") (class "Default")
      (node (ref "R1") (pin "2") (pinfunction "2_2") (pintype "passive"))
      (node (ref "USB") (pin "2") (pinfunction "2_2") (pintype "passive"))
    )
    (net (code "62") (name "Net-(R2-Pad2)") (class "Default")
      (node (ref "R2") (pin "2") (pinfunction "2_2") (pintype "passive"))
      (node (ref "USB") (pin "3") (pinfunction "3_3") (pintype "passive"))
    )
    (net (code "63") (name "Net-(RN1A-2)") (class "Default")
      (node (ref "IN1") (pin "1") (pinfunction "1_1") (pintype "passive"))
      (node (ref "RN1") (pin "8") (pinfunction "2_8") (pintype "passive"))
    )
    (net (code "64") (name "Net-(RN1B-2)") (class "Default")
      (node (ref "IN2") (pin "1") (pinfunction "1_1") (pintype "passive"))
      (node (ref "RN1") (pin "7") (pinfunction "2_7") (pintype "passive"))
    )
    (net (code "65") (name "Net-(RN1C-2)") (class "Default")
      (node (ref "IN3") (pin "1") (pinfunction "1_1") (pintype "passive"))
      (node (ref "RN1") (pin "6") (pinfunction "2_6") (pintype "passive"))
    )
    (net (code "66") (name "Net-(RN1D-2)") (class "Default")
      (node (ref "IN4") (pin "1") (pinfunction "1_1") (pintype "passive"))
      (node (ref "RN1") (pin "5") (pinfunction "2_5") (pintype "passive"))
    )
    (net (code "67") (name "Net-(U4-NR)") (class "Default")
      (node (ref "C19") (pin "1") (pinfunction "1_1") (pintype "passive"))
      (node (ref "U4") (pin "4") (pinfunction "NR_4") (pintype "passive"))
    )
    (net (code "68") (name "VCC") (class "Default")
      (node (ref "C14") (pin "+") (pinfunction "+_+") (pintype "passive"))
      (node (ref "C15") (pin "+") (pinfunction "+_+") (pintype "passive"))
      (node (ref "C16") (pin "1") (pinfunction "1_1") (pintype "passive"))
      (node (ref "C17") (pin "1") (pinfunction "1_1") (pintype "passive"))
      (node (ref "D1") (pin "1") (pinfunction "A_1") (pintype "passive"))
      (node (ref "D2") (pin "1") (pinfunction "A_1") (pintype "passive"))
      (node (ref "Q1") (pin "12") (pinfunction "VS_12") (pintype "power_in"))
      (node (ref "Q1") (pin "9") (pinfunction "VS_9") (pintype "power_in"))
      (node (ref "Q2") (pin "12") (pinfunction "VS_12") (pintype "power_in"))
      (node (ref "Q2") (pin "9") (pinfunction "VS_9") (pintype "power_in"))
      (node (ref "Q3") (pin "1") (pinfunction "S_1") (pintype "bidirectional"))
      (node (ref "Q3") (pin "2") (pinfunction "S_2") (pintype "bidirectional"))
      (node (ref "Q3") (pin "3") (pinfunction "S_3") (pintype "bidirectional"))
      (node (ref "U3") (pin "3") (pinfunction "VI_3") (pintype "input"))
    )
    (net (code "69") (name "unconnected-(U1B-PA8-Pad29)") (class "Default")
      (node (ref "U1") (pin "29") (pinfunction "PA8_29") (pintype "bidirectional"))
    )
    (net (code "70") (name "unconnected-(U1B-PA15-Pad38)") (class "Default")
      (node (ref "U1") (pin "38") (pinfunction "PA15_38") (pintype "bidirectional"))
    )
    (net (code "71") (name "unconnected-(U1C-PA4-Pad14)") (class "Default")
      (node (ref "U1") (pin "14") (pinfunction "PA4_14") (pintype "bidirectional"))
    )
    (net (code "72") (name "unconnected-(U1F-PC13-Pad2)") (class "Default")
      (node (ref "U1") (pin "2") (pinfunction "PC13_2") (pintype "bidirectional"))
    )
    (net (code "73") (name "unconnected-(U1F-PC14-Pad3)") (class "Default")
      (node (ref "U1") (pin "3") (pinfunction "PC14_3") (pintype "bidirectional"))
    )
    (net (code "74") (name "unconnected-(USB-Pad4)") (class "Default")
      (node (ref "USB") (pin "4") (pinfunction "4_4") (pintype "passive"))
    )
  )
)
